# SCH_Schaltung_alt.net
KiCad netlist of a schematic drawn in EasyEDA
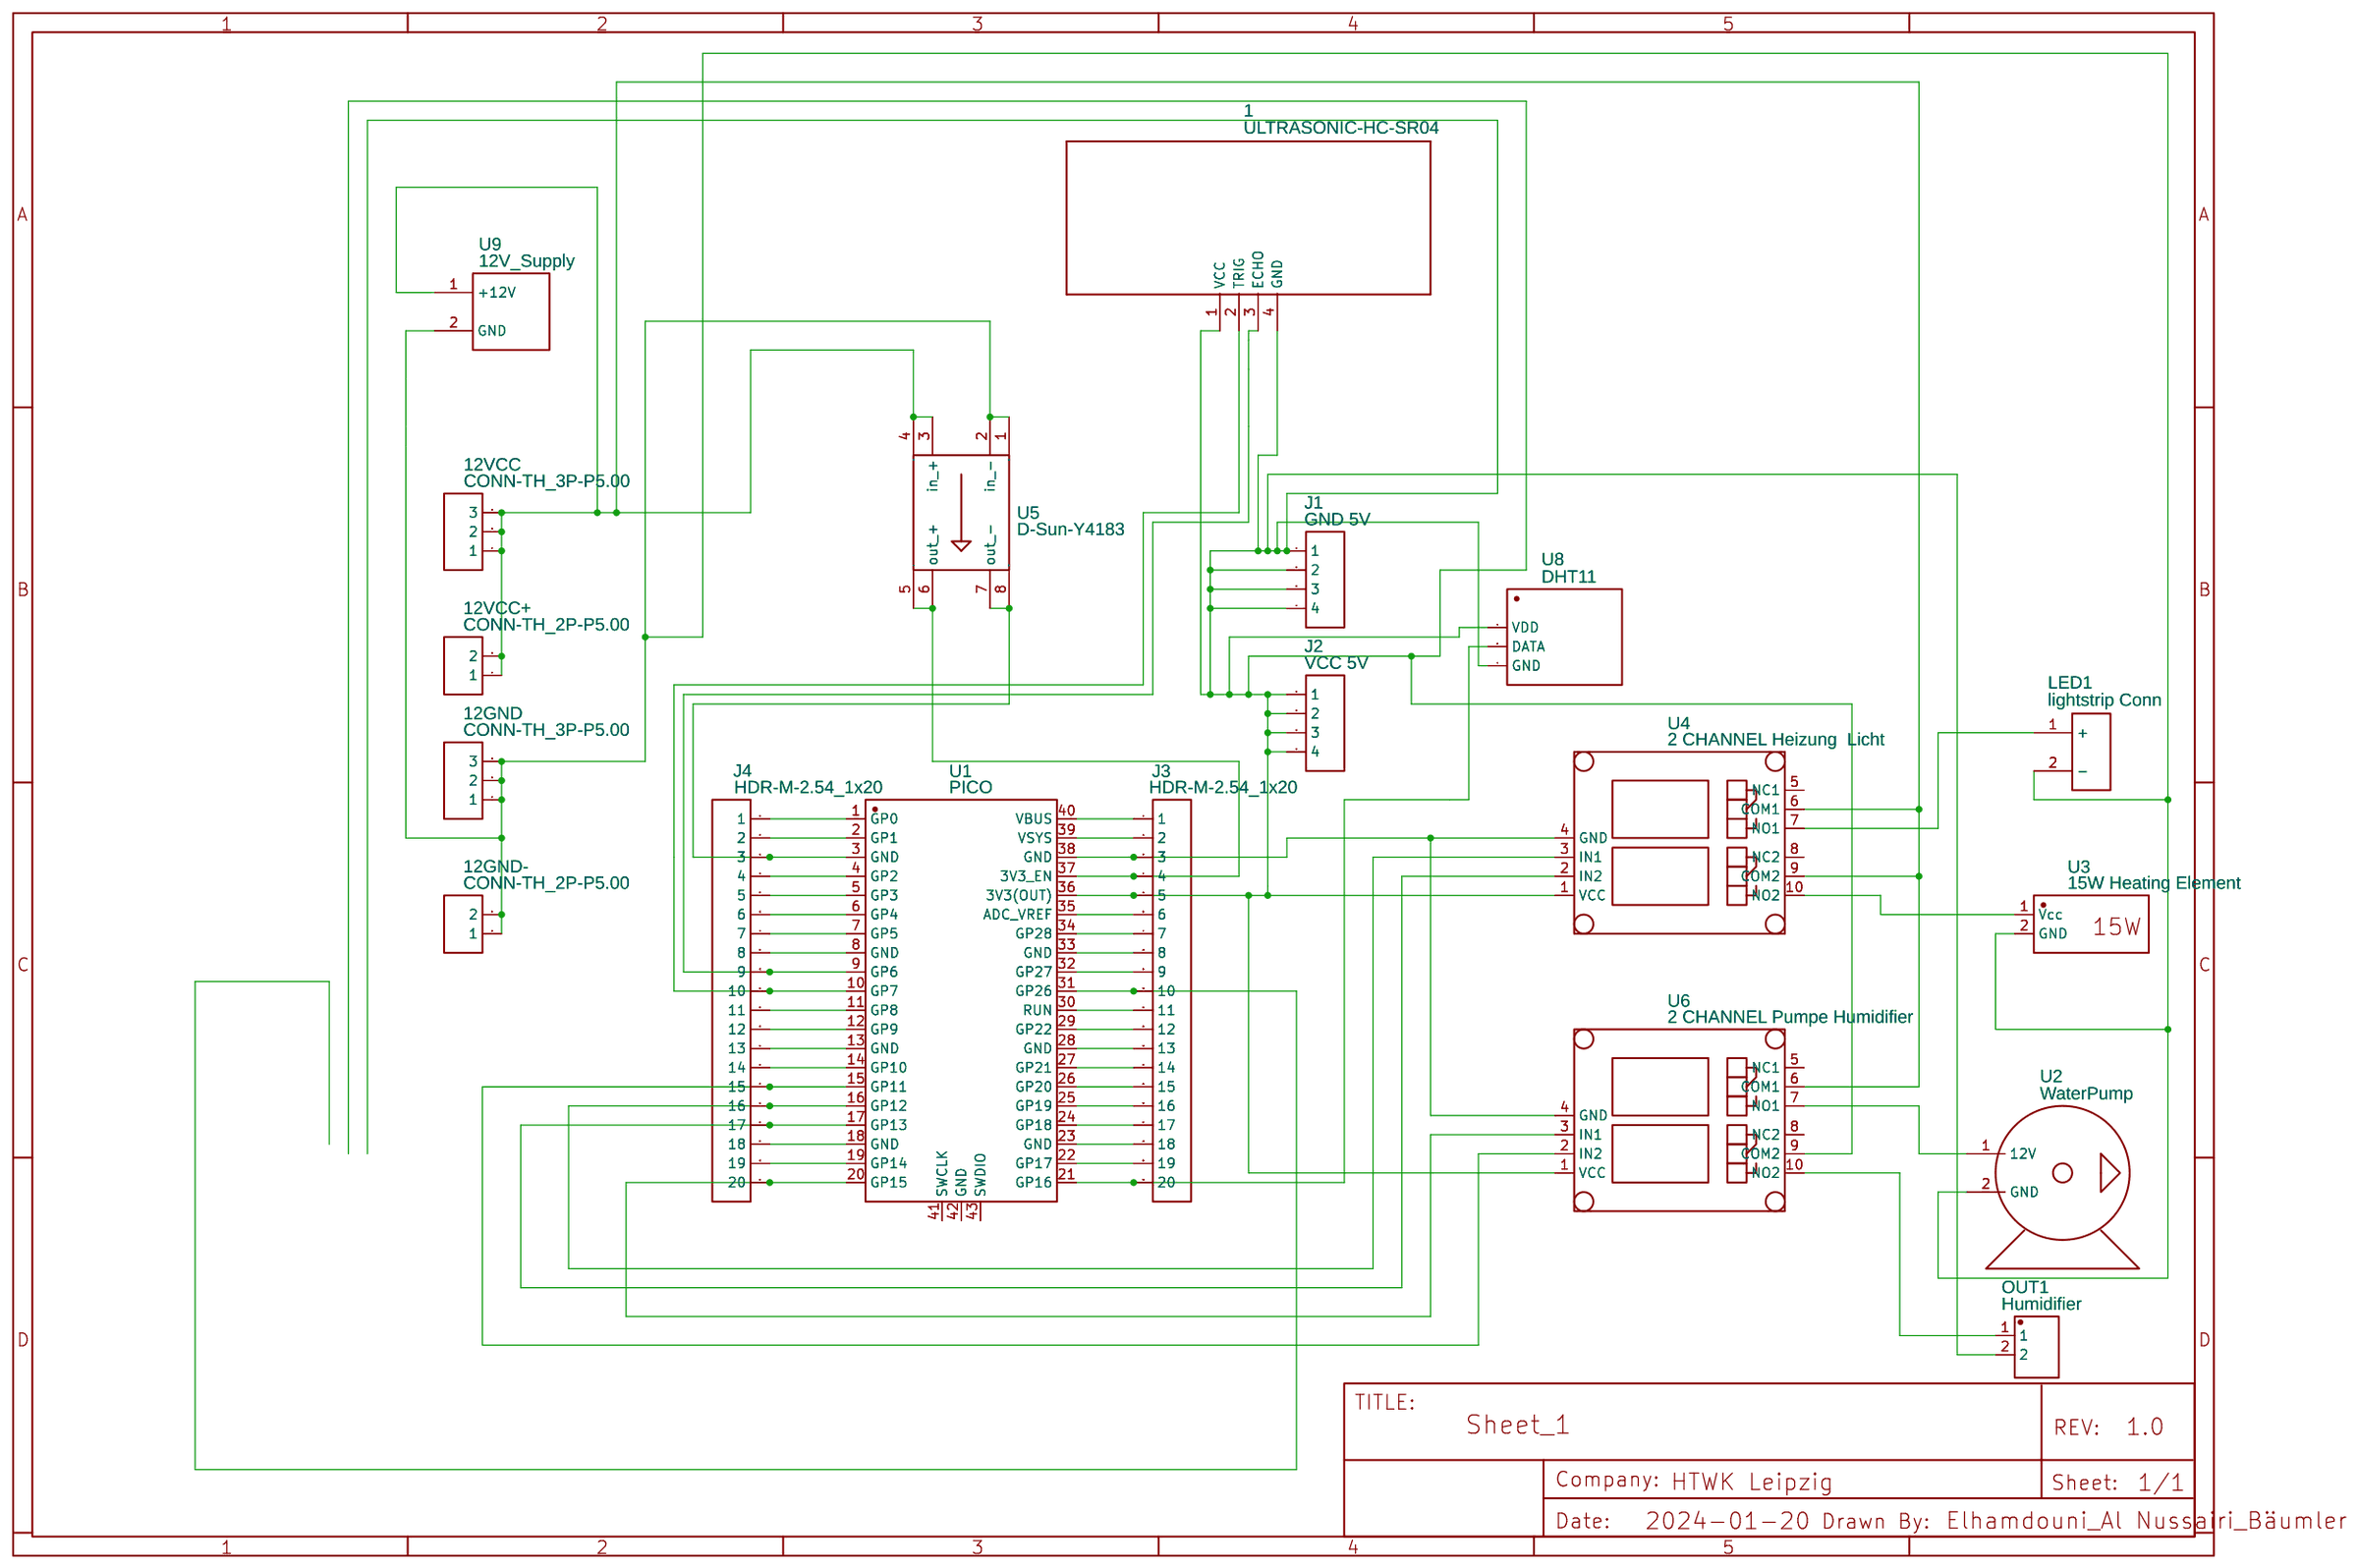
[diagram p0: schematic sheet]

(export (version "E")
  (design (tool "Eeschema 10.0.6"))
  (components
    (comp (ref "1") (value "ULTRASONIC-HC-SR04") (libsource (lib "") (part "ULTRASONIC-HC-SR04")))
    (comp (ref "12GND") (value "CONN-TH_3P-P5.00") (libsource (lib "") (part "CONN-TH_3P-P5.00")))
    (comp (ref "12GND-") (value "CONN-TH_2P-P5.00") (libsource (lib "") (part "CONN-TH_2P-P5.00")))
    (comp (ref "12VCC") (value "CONN-TH_3P-P5.00") (libsource (lib "") (part "CONN-TH_3P-P5.00_1")))
    (comp (ref "12VCC+") (value "CONN-TH_2P-P5.00") (libsource (lib "") (part "CONN-TH_2P-P5.00_1")))
    (comp (ref "J1") (value "GND 5V") (libsource (lib "") (part "HDR-M-2.54_1x4")))
    (comp (ref "J2") (value "VCC 5V") (libsource (lib "") (part "HDR-M-2.54_1x4")))
    (comp (ref "J3") (value "HDR-M-2.54_1x20") (libsource (lib "") (part "HDR-M-2.54_1x20_1")))
    (comp (ref "J4") (value "HDR-M-2.54_1x20") (libsource (lib "") (part "HDR-M-2.54_1x20")))
    (comp (ref "LED1") (value "lightstrip Conn") (libsource (lib "") (part "lightstrip Conn")))
    (comp (ref "OUT1")
      (value "Humidifier")
      (fields (field (name "Manufacturer Part") "WJ2EDGVC-5.08-2P") (field (name "Manufacturer") "ReliaPro"))
      (libsource (lib "") (part "HUMIDIFIER"))
    )
    (comp (ref "U1")
      (value "PICO")
      (fields (field (name "Manufacturer") "Raspberry Pi(树莓派)"))
      (libsource (lib "") (part "PICO"))
    )
    (comp (ref "U2") (value "WaterPump") (libsource (lib "") (part "WaterPump")))
    (comp (ref "U3") (value "15W Heating Element") (libsource (lib "") (part "15W Heating Element")))
    (comp (ref "U4") (value "2 CHANNEL Heizung  Licht") (libsource (lib "") (part "2 CHANNEL RELAY MODULE")))
    (comp (ref "U5") (value "D-Sun-Y4183") (libsource (lib "") (part "D-Sun-Y4183")))
    (comp (ref "U6")
      (value "2 CHANNEL Pumpe Humidifier")
      (libsource (lib "") (part "2 CHANNEL RELAY MODULE"))
    )
    (comp (ref "U8")
      (value "DHT11")
      (fields (field (name "Manufacturer") "AOSONG"))
      (libsource (lib "") (part "DHT11"))
    )
    (comp (ref "U9") (value "12V_Supply") (libsource (lib "") (part "12V_Supply")))
  )
  (nets
    (net (code "1") (name "Net-(1-ECHO)") (class "Default")
      (node (ref "1") (pin "3") (pinfunction "ECHO_3") (pintype "bidirectional"))
      (node (ref "J4") (pin "9") (pinfunction "9_9") (pintype "unspecified"))
      (node (ref "U1") (pin "9") (pinfunction "GP6_9") (pintype "unspecified"))
    )
    (net (code "2") (name "Net-(1-GND)") (class "Default")
      (node (ref "1") (pin "1") (pinfunction "VCC_1") (pintype "bidirectional"))
      (node (ref "1") (pin "4") (pinfunction "GND_4") (pintype "bidirectional"))
      (node (ref "J1") (pin "1") (pinfunction "1_1") (pintype "unspecified"))
      (node (ref "J1") (pin "2") (pinfunction "2_2") (pintype "unspecified"))
      (node (ref "J1") (pin "3") (pinfunction "3_3") (pintype "unspecified"))
      (node (ref "J1") (pin "4") (pinfunction "4_4") (pintype "unspecified"))
      (node (ref "J2") (pin "1") (pinfunction "1_1") (pintype "unspecified"))
      (node (ref "J2") (pin "2") (pinfunction "2_2") (pintype "unspecified"))
      (node (ref "J2") (pin "3") (pinfunction "3_3") (pintype "unspecified"))
      (node (ref "J2") (pin "4") (pinfunction "4_4") (pintype "unspecified"))
      (node (ref "J3") (pin "5") (pinfunction "5_5") (pintype "unspecified"))
      (node (ref "OUT1") (pin "2") (pinfunction "2_2") (pintype "unspecified"))
      (node (ref "U1") (pin "36") (pinfunction "3V3(OUT)_36") (pintype "unspecified"))
      (node (ref "U4") (pin "1") (pinfunction "VCC_1") (pintype "unspecified"))
      (node (ref "U6") (pin "1") (pinfunction "VCC_1") (pintype "unspecified"))
      (node (ref "U6") (pin "9") (pinfunction "COM2_9") (pintype "unspecified"))
      (node (ref "U8") (pin "1") (pinfunction "VDD_1") (pintype "unspecified"))
      (node (ref "U8") (pin "4") (pinfunction "GND_4") (pintype "unspecified"))
    )
    (net (code "3") (name "Net-(1-TRIG)") (class "Default")
      (node (ref "1") (pin "2") (pinfunction "TRIG_2") (pintype "bidirectional"))
      (node (ref "J4") (pin "10") (pinfunction "10_10") (pintype "unspecified"))
      (node (ref "U1") (pin "10") (pinfunction "GP7_10") (pintype "unspecified"))
    )
    (net (code "4") (name "Net-(J3-Pad8)") (class "Default")
      (node (ref "J3") (pin "8") (pinfunction "8_8") (pintype "unspecified"))
      (node (ref "U1") (pin "33") (pinfunction "GND_33") (pintype "unspecified"))
    )
    (net (code "5") (name "Net-(J3-Pad13)") (class "Default")
      (node (ref "J3") (pin "13") (pinfunction "13_13") (pintype "unspecified"))
      (node (ref "U1") (pin "28") (pinfunction "GND_28") (pintype "unspecified"))
    )
    (net (code "6") (name "Net-(J3-Pad18)") (class "Default")
      (node (ref "J3") (pin "18") (pinfunction "18_18") (pintype "unspecified"))
      (node (ref "U1") (pin "23") (pinfunction "GND_23") (pintype "unspecified"))
    )
    (net (code "7") (name "Net-(J4-Pad8)") (class "Default")
      (node (ref "J4") (pin "8") (pinfunction "8_8") (pintype "unspecified"))
      (node (ref "U1") (pin "8") (pinfunction "GND_8") (pintype "unspecified"))
    )
    (net (code "8") (name "Net-(J4-Pad13)") (class "Default")
      (node (ref "J4") (pin "13") (pinfunction "13_13") (pintype "unspecified"))
      (node (ref "U1") (pin "13") (pinfunction "GND_13") (pintype "unspecified"))
    )
    (net (code "9") (name "Net-(J4-Pad18)") (class "Default")
      (node (ref "J4") (pin "18") (pinfunction "18_18") (pintype "unspecified"))
      (node (ref "U1") (pin "18") (pinfunction "GND_18") (pintype "unspecified"))
    )
    (net (code "10") (name "Net-(LED1-+)") (class "Default")
      (node (ref "LED1") (pin "1") (pinfunction "+_1") (pintype "unspecified"))
      (node (ref "U4") (pin "7") (pinfunction "NO1_7") (pintype "unspecified"))
    )
    (net (code "11") (name "Net-(LED1--)") (class "Default")
      (node (ref "12GND") (pin "1") (pinfunction "1_1") (pintype "unspecified"))
      (node (ref "12GND") (pin "2") (pinfunction "2_2") (pintype "unspecified"))
      (node (ref "12GND") (pin "3") (pinfunction "3_3") (pintype "unspecified"))
      (node (ref "12GND-") (pin "1") (pinfunction "1_1") (pintype "unspecified"))
      (node (ref "12GND-") (pin "2") (pinfunction "2_2") (pintype "unspecified"))
      (node (ref "LED1") (pin "2") (pinfunction "-_2") (pintype "unspecified"))
      (node (ref "U2") (pin "2") (pinfunction "GND_2") (pintype "unspecified"))
      (node (ref "U3") (pin "2") (pinfunction "GND_2") (pintype "unspecified"))
      (node (ref "U5") (pin "1") (pinfunction "1_1") (pintype "unspecified"))
      (node (ref "U5") (pin "2") (pinfunction "in_-_2") (pintype "unspecified"))
      (node (ref "U9") (pin "2") (pinfunction "GND_2") (pintype "unspecified"))
    )
    (net (code "12") (name "Net-(U1-3V3_EN)") (class "Default")
      (node (ref "J3") (pin "4") (pinfunction "4_4") (pintype "unspecified"))
      (node (ref "U1") (pin "37") (pinfunction "3V3_EN_37") (pintype "unspecified"))
      (node (ref "U5") (pin "5") (pinfunction "5_5") (pintype "unspecified"))
      (node (ref "U5") (pin "6") (pinfunction "out_+_6") (pintype "unspecified"))
    )
    (net (code "13") (name "Net-(U1-ADC_VREF)") (class "Default")
      (node (ref "J3") (pin "6") (pinfunction "6_6") (pintype "unspecified"))
      (node (ref "U1") (pin "35") (pinfunction "ADC_VREF_35") (pintype "unspecified"))
    )
    (net (code "14") (name "Net-(U1-GP0)") (class "Default")
      (node (ref "J4") (pin "1") (pinfunction "1_1") (pintype "unspecified"))
      (node (ref "U1") (pin "1") (pinfunction "GP0_1") (pintype "unspecified"))
    )
    (net (code "15") (name "Net-(U1-GP1)") (class "Default")
      (node (ref "J4") (pin "2") (pinfunction "2_2") (pintype "unspecified"))
      (node (ref "U1") (pin "2") (pinfunction "GP1_2") (pintype "unspecified"))
    )
    (net (code "16") (name "Net-(U1-GP2)") (class "Default")
      (node (ref "J4") (pin "4") (pinfunction "4_4") (pintype "unspecified"))
      (node (ref "U1") (pin "4") (pinfunction "GP2_4") (pintype "unspecified"))
    )
    (net (code "17") (name "Net-(U1-GP3)") (class "Default")
      (node (ref "J4") (pin "5") (pinfunction "5_5") (pintype "unspecified"))
      (node (ref "U1") (pin "5") (pinfunction "GP3_5") (pintype "unspecified"))
    )
    (net (code "18") (name "Net-(U1-GP4)") (class "Default")
      (node (ref "J4") (pin "6") (pinfunction "6_6") (pintype "unspecified"))
      (node (ref "U1") (pin "6") (pinfunction "GP4_6") (pintype "unspecified"))
    )
    (net (code "19") (name "Net-(U1-GP5)") (class "Default")
      (node (ref "J4") (pin "7") (pinfunction "7_7") (pintype "unspecified"))
      (node (ref "U1") (pin "7") (pinfunction "GP5_7") (pintype "unspecified"))
    )
    (net (code "20") (name "Net-(U1-GP8)") (class "Default")
      (node (ref "J4") (pin "11") (pinfunction "11_11") (pintype "unspecified"))
      (node (ref "U1") (pin "11") (pinfunction "GP8_11") (pintype "unspecified"))
    )
    (net (code "21") (name "Net-(U1-GP9)") (class "Default")
      (node (ref "J4") (pin "12") (pinfunction "12_12") (pintype "unspecified"))
      (node (ref "U1") (pin "12") (pinfunction "GP9_12") (pintype "unspecified"))
    )
    (net (code "22") (name "Net-(U1-GP10)") (class "Default")
      (node (ref "J4") (pin "14") (pinfunction "14_14") (pintype "unspecified"))
      (node (ref "U1") (pin "14") (pinfunction "GP10_14") (pintype "unspecified"))
    )
    (net (code "23") (name "Net-(U1-GP11)") (class "Default")
      (node (ref "J4") (pin "15") (pinfunction "15_15") (pintype "unspecified"))
      (node (ref "U1") (pin "15") (pinfunction "GP11_15") (pintype "unspecified"))
      (node (ref "U6") (pin "2") (pinfunction "IN2_2") (pintype "unspecified"))
    )
    (net (code "24") (name "Net-(U1-GP12)") (class "Default")
      (node (ref "J4") (pin "16") (pinfunction "16_16") (pintype "unspecified"))
      (node (ref "U1") (pin "16") (pinfunction "GP12_16") (pintype "unspecified"))
      (node (ref "U4") (pin "3") (pinfunction "IN1_3") (pintype "unspecified"))
    )
    (net (code "25") (name "Net-(U1-GP13)") (class "Default")
      (node (ref "J4") (pin "17") (pinfunction "17_17") (pintype "unspecified"))
      (node (ref "U1") (pin "17") (pinfunction "GP13_17") (pintype "unspecified"))
      (node (ref "U4") (pin "2") (pinfunction "IN2_2") (pintype "unspecified"))
    )
    (net (code "26") (name "Net-(U1-GP14)") (class "Default")
      (node (ref "J4") (pin "19") (pinfunction "19_19") (pintype "unspecified"))
      (node (ref "U1") (pin "19") (pinfunction "GP14_19") (pintype "unspecified"))
    )
    (net (code "27") (name "Net-(U1-GP15)") (class "Default")
      (node (ref "J4") (pin "20") (pinfunction "20_20") (pintype "unspecified"))
      (node (ref "U1") (pin "20") (pinfunction "GP15_20") (pintype "unspecified"))
      (node (ref "U6") (pin "3") (pinfunction "IN1_3") (pintype "unspecified"))
    )
    (net (code "28") (name "Net-(U1-GP16)") (class "Default")
      (node (ref "J3") (pin "20") (pinfunction "20_20") (pintype "unspecified"))
      (node (ref "U1") (pin "21") (pinfunction "GP16_21") (pintype "unspecified"))
      (node (ref "U8") (pin "2") (pinfunction "DATA_2") (pintype "unspecified"))
    )
    (net (code "29") (name "Net-(U1-GP17)") (class "Default")
      (node (ref "J3") (pin "19") (pinfunction "19_19") (pintype "unspecified"))
      (node (ref "U1") (pin "22") (pinfunction "GP17_22") (pintype "unspecified"))
    )
    (net (code "30") (name "Net-(U1-GP18)") (class "Default")
      (node (ref "J3") (pin "17") (pinfunction "17_17") (pintype "unspecified"))
      (node (ref "U1") (pin "24") (pinfunction "GP18_24") (pintype "unspecified"))
    )
    (net (code "31") (name "Net-(U1-GP19)") (class "Default")
      (node (ref "J3") (pin "16") (pinfunction "16_16") (pintype "unspecified"))
      (node (ref "U1") (pin "25") (pinfunction "GP19_25") (pintype "unspecified"))
    )
    (net (code "32") (name "Net-(U1-GP20)") (class "Default")
      (node (ref "J3") (pin "15") (pinfunction "15_15") (pintype "unspecified"))
      (node (ref "U1") (pin "26") (pinfunction "GP20_26") (pintype "unspecified"))
    )
    (net (code "33") (name "Net-(U1-GP21)") (class "Default")
      (node (ref "J3") (pin "14") (pinfunction "14_14") (pintype "unspecified"))
      (node (ref "U1") (pin "27") (pinfunction "GP21_27") (pintype "unspecified"))
    )
    (net (code "34") (name "Net-(U1-GP22)") (class "Default")
      (node (ref "J3") (pin "12") (pinfunction "12_12") (pintype "unspecified"))
      (node (ref "U1") (pin "29") (pinfunction "GP22_29") (pintype "unspecified"))
    )
    (net (code "35") (name "Net-(U1-GP26)") (class "Default")
      (node (ref "J3") (pin "10") (pinfunction "10_10") (pintype "unspecified"))
      (node (ref "U1") (pin "31") (pinfunction "GP26_31") (pintype "unspecified"))
    )
    (net (code "36") (name "Net-(U1-GP27)") (class "Default")
      (node (ref "J3") (pin "9") (pinfunction "9_9") (pintype "unspecified"))
      (node (ref "U1") (pin "32") (pinfunction "GP27_32") (pintype "unspecified"))
    )
    (net (code "37") (name "Net-(U1-GP28)") (class "Default")
      (node (ref "J3") (pin "7") (pinfunction "7_7") (pintype "unspecified"))
      (node (ref "U1") (pin "34") (pinfunction "GP28_34") (pintype "unspecified"))
    )
    (net (code "38") (name "Net-(U1-RUN)") (class "Default")
      (node (ref "J3") (pin "11") (pinfunction "11_11") (pintype "unspecified"))
      (node (ref "U1") (pin "30") (pinfunction "RUN_30") (pintype "unspecified"))
    )
    (net (code "39") (name "Net-(U1-VBUS)") (class "Default")
      (node (ref "J3") (pin "1") (pinfunction "1_1") (pintype "unspecified"))
      (node (ref "U1") (pin "40") (pinfunction "VBUS_40") (pintype "unspecified"))
    )
    (net (code "40") (name "Net-(U1-VSYS)") (class "Default")
      (node (ref "J3") (pin "2") (pinfunction "2_2") (pintype "unspecified"))
      (node (ref "U1") (pin "39") (pinfunction "VSYS_39") (pintype "unspecified"))
    )
    (net (code "41") (name "Net-(U2-12V)") (class "Default")
      (node (ref "U2") (pin "1") (pinfunction "12V_1") (pintype "unspecified"))
      (node (ref "U6") (pin "7") (pinfunction "NO1_7") (pintype "unspecified"))
    )
    (net (code "42") (name "Net-(U3-Vcc)") (class "Default")
      (node (ref "U3") (pin "1") (pinfunction "Vcc_1") (pintype "unspecified"))
      (node (ref "U4") (pin "10") (pinfunction "NO2_10") (pintype "unspecified"))
    )
    (net (code "43") (name "Net-(U4-COM1)") (class "Default")
      (node (ref "12VCC") (pin "1") (pinfunction "1_1") (pintype "unspecified"))
      (node (ref "12VCC") (pin "2") (pinfunction "2_2") (pintype "unspecified"))
      (node (ref "12VCC") (pin "3") (pinfunction "3_3") (pintype "unspecified"))
      (node (ref "12VCC+") (pin "1") (pinfunction "1_1") (pintype "unspecified"))
      (node (ref "12VCC+") (pin "2") (pinfunction "2_2") (pintype "unspecified"))
      (node (ref "U4") (pin "6") (pinfunction "COM1_6") (pintype "unspecified"))
      (node (ref "U4") (pin "9") (pinfunction "COM2_9") (pintype "unspecified"))
      (node (ref "U5") (pin "3") (pinfunction "in_+_3") (pintype "unspecified"))
      (node (ref "U5") (pin "4") (pinfunction "4_4") (pintype "unspecified"))
      (node (ref "U6") (pin "6") (pinfunction "COM1_6") (pintype "unspecified"))
      (node (ref "U9") (pin "1") (pinfunction "+12V_1") (pintype "unspecified"))
    )
    (net (code "44") (name "Net-(U4-GND)") (class "Default")
      (node (ref "J3") (pin "3") (pinfunction "3_3") (pintype "unspecified"))
      (node (ref "U1") (pin "38") (pinfunction "GND_38") (pintype "unspecified"))
      (node (ref "U4") (pin "4") (pinfunction "GND_4") (pintype "unspecified"))
      (node (ref "U6") (pin "4") (pinfunction "GND_4") (pintype "unspecified"))
    )
    (net (code "45") (name "Net-(U5-out_-)") (class "Default")
      (node (ref "J4") (pin "3") (pinfunction "3_3") (pintype "unspecified"))
      (node (ref "U1") (pin "3") (pinfunction "GND_3") (pintype "unspecified"))
      (node (ref "U5") (pin "7") (pinfunction "out_-_7") (pintype "unspecified"))
      (node (ref "U5") (pin "8") (pinfunction "8_8") (pintype "unspecified"))
    )
    (net (code "46") (name "Net-(U6-NO2)") (class "Default")
      (node (ref "OUT1") (pin "1") (pinfunction "1_1") (pintype "unspecified"))
      (node (ref "U6") (pin "10") (pinfunction "NO2_10") (pintype "unspecified"))
    )
    (net (code "47") (name "unconnected-(U1-GND-Pad42)") (class "Default")
      (node (ref "U1") (pin "42") (pinfunction "GND_42") (pintype "unspecified"))
    )
    (net (code "48") (name "unconnected-(U1-SWCLK-Pad41)") (class "Default")
      (node (ref "U1") (pin "41") (pinfunction "SWCLK_41") (pintype "unspecified"))
    )
    (net (code "49") (name "unconnected-(U1-SWDIO-Pad43)") (class "Default")
      (node (ref "U1") (pin "43") (pinfunction "SWDIO_43") (pintype "unspecified"))
    )
    (net (code "50") (name "unconnected-(U4-NC1-Pad5)") (class "Default")
      (node (ref "U4") (pin "5") (pinfunction "NC1_5") (pintype "unspecified"))
    )
    (net (code "51") (name "unconnected-(U4-NC2-Pad8)") (class "Default")
      (node (ref "U4") (pin "8") (pinfunction "NC2_8") (pintype "unspecified"))
    )
    (net (code "52") (name "unconnected-(U6-NC1-Pad5)") (class "Default")
      (node (ref "U6") (pin "5") (pinfunction "NC1_5") (pintype "unspecified"))
    )
    (net (code "53") (name "unconnected-(U6-NC2-Pad8)") (class "Default")
      (node (ref "U6") (pin "8") (pinfunction "NC2_8") (pintype "unspecified"))
    )
  )
)
